# Iris_v1.net
KiCad netlist of a schematic drawn in EAGLE
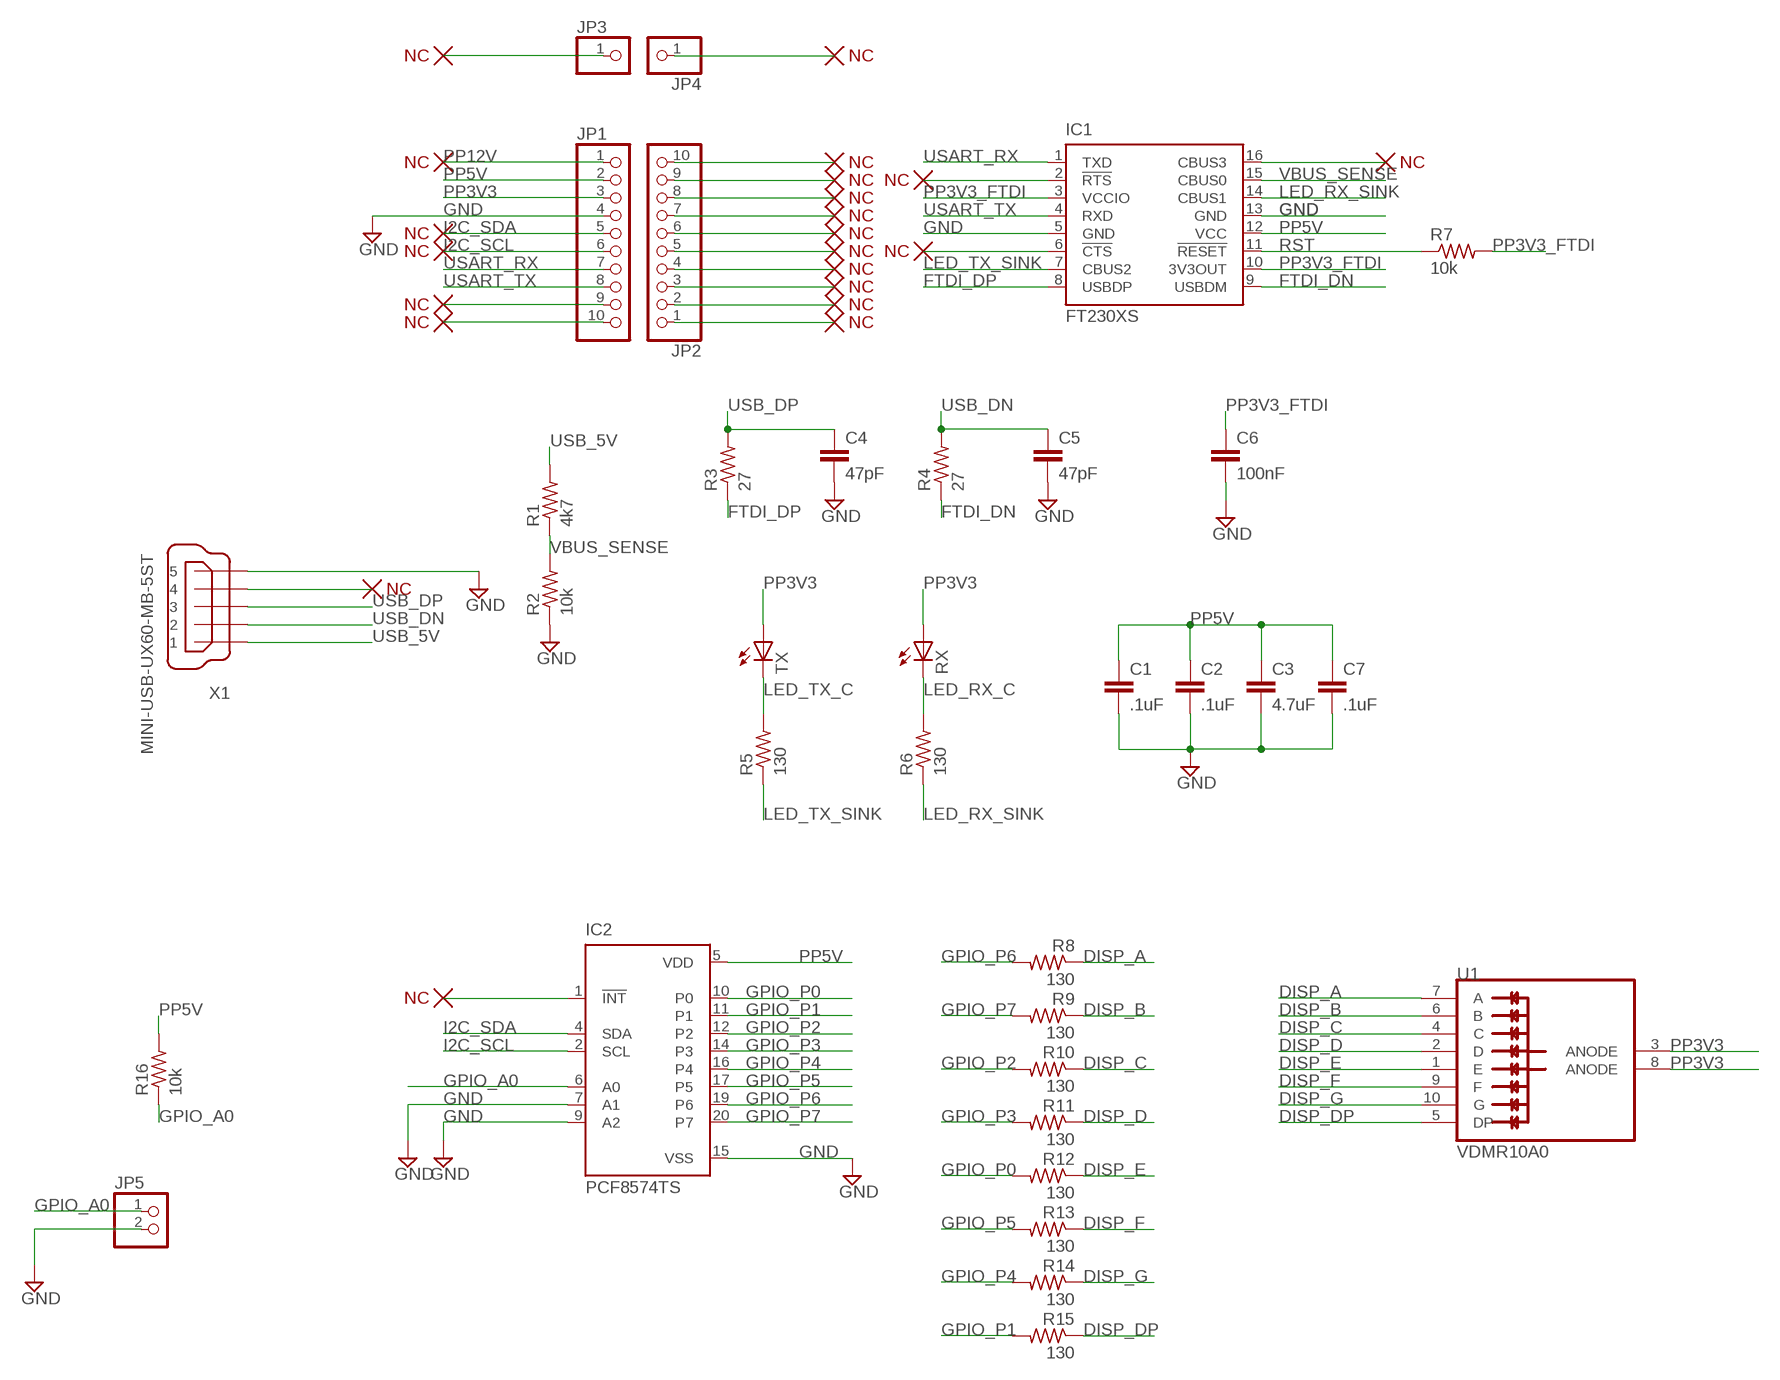
[diagram p0: schematic, sheet 1]

(export (version "E")
  (design (tool "Eeschema 10.0.6"))
  (components
    (comp (ref "C1")
      (value ".1uF")
      (footprint "eagle-import:C0402")
      (libsource (lib "eagle-import") (part "C-EUC0402"))
    )
    (comp (ref "C2")
      (value ".1uF")
      (footprint "eagle-import:C0402")
      (libsource (lib "eagle-import") (part "C-EUC0402"))
    )
    (comp (ref "C3")
      (value "4.7uF")
      (footprint "eagle-import:C0603")
      (libsource (lib "eagle-import") (part "C-EUC0603"))
    )
    (comp (ref "C4")
      (value "47pF")
      (footprint "eagle-import:C0402")
      (libsource (lib "eagle-import") (part "C-EUC0402"))
    )
    (comp (ref "C5")
      (value "47pF")
      (footprint "eagle-import:C0402")
      (libsource (lib "eagle-import") (part "C-EUC0402"))
    )
    (comp (ref "C6")
      (value "100nF")
      (footprint "eagle-import:C0402")
      (libsource (lib "eagle-import") (part "C-EUC0402"))
    )
    (comp (ref "C7")
      (value ".1uF")
      (footprint "eagle-import:C0402")
      (libsource (lib "eagle-import") (part "C-EUC0402"))
    )
    (comp (ref "IC1")
      (value "FT230XS")
      (footprint "eagle-import:SSOP16")
      (libsource (lib "eagle-import") (part "FT230XS"))
    )
    (comp (ref "IC2")
      (value "PCF8574TS")
      (footprint "eagle-import:SSOP20")
      (fields (field (name "MPN") "PCF8574TS/3,118"))
      (libsource (lib "eagle-import") (part "PCF8574TS"))
    )
    (comp (ref "JP1")
      (value "PINHD-1X10")
      (footprint "eagle-import:1X10")
      (libsource (lib "eagle-import") (part "PINHD-1X10"))
    )
    (comp (ref "JP2")
      (value "PINHD-1X10")
      (footprint "eagle-import:1X10")
      (libsource (lib "eagle-import") (part "PINHD-1X10"))
    )
    (comp (ref "JP3")
      (value "PINHD-1X1")
      (footprint "eagle-import:1X01")
      (libsource (lib "eagle-import") (part "PINHD-1X1"))
    )
    (comp (ref "JP4")
      (value "PINHD-1X1")
      (footprint "eagle-import:1X01")
      (libsource (lib "eagle-import") (part "PINHD-1X1"))
    )
    (comp (ref "JP5")
      (value "PINHD-1X2")
      (footprint "eagle-import:1X02")
      (libsource (lib "eagle-import") (part "PINHD-1X2"))
    )
    (comp (ref "R1")
      (value "4k7")
      (footprint "eagle-import:R0402")
      (libsource (lib "eagle-import") (part "resistor_R-US_R0402"))
    )
    (comp (ref "R2")
      (value "10k")
      (footprint "eagle-import:R0402")
      (libsource (lib "eagle-import") (part "resistor_R-US_R0402"))
    )
    (comp (ref "R3")
      (value "27")
      (footprint "eagle-import:R0402")
      (libsource (lib "eagle-import") (part "resistor_R-US_R0402"))
    )
    (comp (ref "R4")
      (value "27")
      (footprint "eagle-import:R0402")
      (libsource (lib "eagle-import") (part "resistor_R-US_R0402"))
    )
    (comp (ref "R5")
      (value "130")
      (footprint "eagle-import:R0402")
      (libsource (lib "eagle-import") (part "resistor_R-US_R0402"))
    )
    (comp (ref "R6")
      (value "130")
      (footprint "eagle-import:R0402")
      (libsource (lib "eagle-import") (part "resistor_R-US_R0402"))
    )
    (comp (ref "R7")
      (value "10k")
      (footprint "eagle-import:R0603")
      (libsource (lib "eagle-import") (part "R-US_R0603"))
    )
    (comp (ref "R8")
      (value "130")
      (footprint "eagle-import:R0402")
      (libsource (lib "eagle-import") (part "resistor_R-US_R0402"))
    )
    (comp (ref "R9")
      (value "130")
      (footprint "eagle-import:R0402")
      (libsource (lib "eagle-import") (part "resistor_R-US_R0402"))
    )
    (comp (ref "R10")
      (value "130")
      (footprint "eagle-import:R0402")
      (libsource (lib "eagle-import") (part "resistor_R-US_R0402"))
    )
    (comp (ref "R11")
      (value "130")
      (footprint "eagle-import:R0402")
      (libsource (lib "eagle-import") (part "resistor_R-US_R0402"))
    )
    (comp (ref "R12")
      (value "130")
      (footprint "eagle-import:R0402")
      (libsource (lib "eagle-import") (part "resistor_R-US_R0402"))
    )
    (comp (ref "R13")
      (value "130")
      (footprint "eagle-import:R0402")
      (libsource (lib "eagle-import") (part "resistor_R-US_R0402"))
    )
    (comp (ref "R14")
      (value "130")
      (footprint "eagle-import:R0402")
      (libsource (lib "eagle-import") (part "resistor_R-US_R0402"))
    )
    (comp (ref "R15")
      (value "130")
      (footprint "eagle-import:R0402")
      (libsource (lib "eagle-import") (part "resistor_R-US_R0402"))
    )
    (comp (ref "R16")
      (value "10k")
      (footprint "eagle-import:R0402")
      (libsource (lib "eagle-import") (part "resistor_R-US_R0402"))
    )
    (comp (ref "RX")
      (value "LEDCHIP-LED0603")
      (footprint "eagle-import:CHIP-LED0603")
      (libsource (lib "eagle-import") (part "LEDCHIP-LED0603"))
    )
    (comp (ref "TX")
      (value "LEDCHIP-LED0603")
      (footprint "eagle-import:CHIP-LED0603")
      (libsource (lib "eagle-import") (part "LEDCHIP-LED0603"))
    )
    (comp (ref "U1")
      (value "VDMR10.0")
      (footprint "eagle-import:VDMR10A0")
      (libsource (lib "eagle-import") (part "VDMR10.0"))
    )
    (comp (ref "X1")
      (value "MINI-USB-UX60-MB-5ST")
      (footprint "eagle-import:UX60-MB-5ST")
      (libsource (lib "eagle-import") (part "MINI-USB-UX60-MB-5ST"))
    )
  )
  (nets
    (net (code "1") (name "/DISP_A") (class "Default")
      (node (ref "R8") (pin "1") (pinfunction "1_1") (pintype "passive"))
      (node (ref "U1") (pin "7") (pinfunction "A_7") (pintype "bidirectional"))
    )
    (net (code "2") (name "/DISP_B") (class "Default")
      (node (ref "R9") (pin "1") (pinfunction "1_1") (pintype "passive"))
      (node (ref "U1") (pin "6") (pinfunction "B_6") (pintype "bidirectional"))
    )
    (net (code "3") (name "/DISP_C") (class "Default")
      (node (ref "R10") (pin "1") (pinfunction "1_1") (pintype "passive"))
      (node (ref "U1") (pin "4") (pinfunction "C_4") (pintype "bidirectional"))
    )
    (net (code "4") (name "/DISP_D") (class "Default")
      (node (ref "R11") (pin "1") (pinfunction "1_1") (pintype "passive"))
      (node (ref "U1") (pin "2") (pinfunction "D_2") (pintype "bidirectional"))
    )
    (net (code "5") (name "/DISP_DP") (class "Default")
      (node (ref "R15") (pin "1") (pinfunction "1_1") (pintype "passive"))
      (node (ref "U1") (pin "5") (pinfunction "DP_5") (pintype "bidirectional"))
    )
    (net (code "6") (name "/DISP_E") (class "Default")
      (node (ref "R12") (pin "1") (pinfunction "1_1") (pintype "passive"))
      (node (ref "U1") (pin "1") (pinfunction "E_1") (pintype "bidirectional"))
    )
    (net (code "7") (name "/DISP_F") (class "Default")
      (node (ref "R13") (pin "1") (pinfunction "1_1") (pintype "passive"))
      (node (ref "U1") (pin "9") (pinfunction "F_9") (pintype "bidirectional"))
    )
    (net (code "8") (name "/DISP_G") (class "Default")
      (node (ref "R14") (pin "1") (pinfunction "1_1") (pintype "passive"))
      (node (ref "U1") (pin "10") (pinfunction "G_10") (pintype "bidirectional"))
    )
    (net (code "9") (name "/FTDI_DN") (class "Default")
      (node (ref "IC1") (pin "9") (pinfunction "USBDM_9") (pintype "input"))
      (node (ref "R4") (pin "1") (pinfunction "1_1") (pintype "passive"))
    )
    (net (code "10") (name "/FTDI_DP") (class "Default")
      (node (ref "IC1") (pin "8") (pinfunction "USBDP_8") (pintype "input"))
      (node (ref "R3") (pin "1") (pinfunction "1_1") (pintype "passive"))
    )
    (net (code "11") (name "/GPIO_A0") (class "Default")
      (node (ref "IC2") (pin "6") (pinfunction "A0_6") (pintype "input"))
      (node (ref "JP5") (pin "1") (pinfunction "1_1") (pintype "passive"))
      (node (ref "R16") (pin "1") (pinfunction "1_1") (pintype "passive"))
    )
    (net (code "12") (name "/GPIO_P0") (class "Default")
      (node (ref "IC2") (pin "10") (pinfunction "P0_10") (pintype "bidirectional"))
      (node (ref "R12") (pin "2") (pinfunction "2_2") (pintype "passive"))
    )
    (net (code "13") (name "/GPIO_P1") (class "Default")
      (node (ref "IC2") (pin "11") (pinfunction "P1_11") (pintype "bidirectional"))
      (node (ref "R15") (pin "2") (pinfunction "2_2") (pintype "passive"))
    )
    (net (code "14") (name "/GPIO_P2") (class "Default")
      (node (ref "IC2") (pin "12") (pinfunction "P2_12") (pintype "bidirectional"))
      (node (ref "R10") (pin "2") (pinfunction "2_2") (pintype "passive"))
    )
    (net (code "15") (name "/GPIO_P3") (class "Default")
      (node (ref "IC2") (pin "14") (pinfunction "P3_14") (pintype "bidirectional"))
      (node (ref "R11") (pin "2") (pinfunction "2_2") (pintype "passive"))
    )
    (net (code "16") (name "/GPIO_P4") (class "Default")
      (node (ref "IC2") (pin "16") (pinfunction "P4_16") (pintype "bidirectional"))
      (node (ref "R14") (pin "2") (pinfunction "2_2") (pintype "passive"))
    )
    (net (code "17") (name "/GPIO_P5") (class "Default")
      (node (ref "IC2") (pin "17") (pinfunction "P5_17") (pintype "bidirectional"))
      (node (ref "R13") (pin "2") (pinfunction "2_2") (pintype "passive"))
    )
    (net (code "18") (name "/GPIO_P6") (class "Default")
      (node (ref "IC2") (pin "19") (pinfunction "P6_19") (pintype "bidirectional"))
      (node (ref "R8") (pin "2") (pinfunction "2_2") (pintype "passive"))
    )
    (net (code "19") (name "/GPIO_P7") (class "Default")
      (node (ref "IC2") (pin "20") (pinfunction "P7_20") (pintype "bidirectional"))
      (node (ref "R9") (pin "2") (pinfunction "2_2") (pintype "passive"))
    )
    (net (code "20") (name "/I2C_SCL") (class "Default")
      (node (ref "IC2") (pin "2") (pinfunction "SCL_2") (pintype "input"))
      (node (ref "JP1") (pin "6") (pinfunction "6_6") (pintype "passive"))
    )
    (net (code "21") (name "/I2C_SDA") (class "Default")
      (node (ref "IC2") (pin "4") (pinfunction "SDA_4") (pintype "bidirectional"))
      (node (ref "JP1") (pin "5") (pinfunction "5_5") (pintype "passive"))
    )
    (net (code "22") (name "/LED_RX_C") (class "Default")
      (node (ref "R6") (pin "2") (pinfunction "2_2") (pintype "passive"))
      (node (ref "RX") (pin "C") (pinfunction "C_C") (pintype "passive"))
    )
    (net (code "23") (name "/LED_RX_SINK") (class "Default")
      (node (ref "IC1") (pin "14") (pinfunction "CBUS1_14") (pintype "bidirectional"))
      (node (ref "R6") (pin "1") (pinfunction "1_1") (pintype "passive"))
    )
    (net (code "24") (name "/LED_TX_C") (class "Default")
      (node (ref "R5") (pin "2") (pinfunction "2_2") (pintype "passive"))
      (node (ref "TX") (pin "C") (pinfunction "C_C") (pintype "passive"))
    )
    (net (code "25") (name "/LED_TX_SINK") (class "Default")
      (node (ref "IC1") (pin "7") (pinfunction "CBUS2_7") (pintype "bidirectional"))
      (node (ref "R5") (pin "1") (pinfunction "1_1") (pintype "passive"))
    )
    (net (code "26") (name "/PP3V3") (class "Default")
      (node (ref "JP1") (pin "3") (pinfunction "3_3") (pintype "passive"))
      (node (ref "RX") (pin "A") (pinfunction "A_A") (pintype "passive"))
      (node (ref "TX") (pin "A") (pinfunction "A_A") (pintype "passive"))
      (node (ref "U1") (pin "3") (pinfunction "ANODE_3") (pintype "bidirectional"))
      (node (ref "U1") (pin "8") (pinfunction "ANODE_8") (pintype "bidirectional"))
    )
    (net (code "27") (name "/PP3V3_FTDI") (class "Default")
      (node (ref "C6") (pin "1") (pinfunction "1_1") (pintype "passive"))
      (node (ref "IC1") (pin "10") (pinfunction "3V3OUT_10") (pintype "output"))
      (node (ref "IC1") (pin "3") (pinfunction "VCCIO_3") (pintype "power_in"))
      (node (ref "R7") (pin "2") (pinfunction "2_2") (pintype "passive"))
    )
    (net (code "28") (name "/PP5V") (class "Default")
      (node (ref "C1") (pin "1") (pinfunction "1_1") (pintype "passive"))
      (node (ref "C2") (pin "1") (pinfunction "1_1") (pintype "passive"))
      (node (ref "C3") (pin "1") (pinfunction "1_1") (pintype "passive"))
      (node (ref "C7") (pin "1") (pinfunction "1_1") (pintype "passive"))
      (node (ref "IC1") (pin "12") (pinfunction "VCC_12") (pintype "power_in"))
      (node (ref "IC2") (pin "5") (pinfunction "VDD_5") (pintype "power_in"))
      (node (ref "JP1") (pin "2") (pinfunction "2_2") (pintype "passive"))
      (node (ref "R16") (pin "2") (pinfunction "2_2") (pintype "passive"))
    )
    (net (code "29") (name "/PP12V") (class "Default")
      (node (ref "JP1") (pin "1") (pinfunction "1_1") (pintype "passive"))
    )
    (net (code "30") (name "/RST") (class "Default")
      (node (ref "IC1") (pin "11") (pinfunction "~{RESET}_11") (pintype "input"))
      (node (ref "R7") (pin "1") (pinfunction "1_1") (pintype "passive"))
    )
    (net (code "31") (name "/USART_RX") (class "Default")
      (node (ref "IC1") (pin "1") (pinfunction "TXD_1") (pintype "output"))
      (node (ref "JP1") (pin "7") (pinfunction "7_7") (pintype "passive"))
    )
    (net (code "32") (name "/USART_TX") (class "Default")
      (node (ref "IC1") (pin "4") (pinfunction "RXD_4") (pintype "input"))
      (node (ref "JP1") (pin "8") (pinfunction "8_8") (pintype "passive"))
    )
    (net (code "33") (name "/USB_5V") (class "Default")
      (node (ref "R1") (pin "2") (pinfunction "2_2") (pintype "passive"))
      (node (ref "X1") (pin "1") (pinfunction "1_1") (pintype "input"))
    )
    (net (code "34") (name "/USB_DN") (class "Default")
      (node (ref "C5") (pin "1") (pinfunction "1_1") (pintype "passive"))
      (node (ref "R4") (pin "2") (pinfunction "2_2") (pintype "passive"))
      (node (ref "X1") (pin "2") (pinfunction "2_2") (pintype "input"))
    )
    (net (code "35") (name "/USB_DP") (class "Default")
      (node (ref "C4") (pin "1") (pinfunction "1_1") (pintype "passive"))
      (node (ref "R3") (pin "2") (pinfunction "2_2") (pintype "passive"))
      (node (ref "X1") (pin "3") (pinfunction "3_3") (pintype "input"))
    )
    (net (code "36") (name "/VBUS_SENSE") (class "Default")
      (node (ref "IC1") (pin "15") (pinfunction "CBUS0_15") (pintype "bidirectional"))
      (node (ref "R1") (pin "1") (pinfunction "1_1") (pintype "passive"))
      (node (ref "R2") (pin "2") (pinfunction "2_2") (pintype "passive"))
    )
    (net (code "37") (name "GND") (class "Default")
      (node (ref "C1") (pin "2") (pinfunction "2_2") (pintype "passive"))
      (node (ref "C2") (pin "2") (pinfunction "2_2") (pintype "passive"))
      (node (ref "C3") (pin "2") (pinfunction "2_2") (pintype "passive"))
      (node (ref "C4") (pin "2") (pinfunction "2_2") (pintype "passive"))
      (node (ref "C5") (pin "2") (pinfunction "2_2") (pintype "passive"))
      (node (ref "C6") (pin "2") (pinfunction "2_2") (pintype "passive"))
      (node (ref "C7") (pin "2") (pinfunction "2_2") (pintype "passive"))
      (node (ref "IC1") (pin "13") (pinfunction "GND_13") (pintype "power_in"))
      (node (ref "IC1") (pin "5") (pinfunction "GND_5") (pintype "power_in"))
      (node (ref "IC2") (pin "15") (pinfunction "VSS_15") (pintype "power_in"))
      (node (ref "IC2") (pin "7") (pinfunction "A1_7") (pintype "input"))
      (node (ref "IC2") (pin "9") (pinfunction "A2_9") (pintype "input"))
      (node (ref "JP1") (pin "4") (pinfunction "4_4") (pintype "passive"))
      (node (ref "JP5") (pin "2") (pinfunction "2_2") (pintype "passive"))
      (node (ref "R2") (pin "1") (pinfunction "1_1") (pintype "passive"))
      (node (ref "X1") (pin "5") (pinfunction "5_5") (pintype "input"))
    )
    (net (code "38") (name "unconnected-(IC1-CBUS3-Pad16)") (class "Default")
      (node (ref "IC1") (pin "16") (pinfunction "CBUS3_16") (pintype "bidirectional"))
    )
    (net (code "39") (name "unconnected-(IC1-~{CTS}-Pad6)") (class "Default")
      (node (ref "IC1") (pin "6") (pinfunction "~{CTS}_6") (pintype "input"))
    )
    (net (code "40") (name "unconnected-(IC1-~{RTS}-Pad2)") (class "Default")
      (node (ref "IC1") (pin "2") (pinfunction "~{RTS}_2") (pintype "output"))
    )
    (net (code "41") (name "unconnected-(IC2-~{INT}-Pad1)") (class "Default")
      (node (ref "IC2") (pin "1") (pinfunction "~{INT}_1") (pintype "output"))
    )
    (net (code "42") (name "unconnected-(JP1-Pad9)") (class "Default")
      (node (ref "JP1") (pin "9") (pinfunction "9_9") (pintype "passive"))
    )
    (net (code "43") (name "unconnected-(JP1-Pad10)") (class "Default")
      (node (ref "JP1") (pin "10") (pinfunction "10_10") (pintype "passive"))
    )
    (net (code "44") (name "unconnected-(JP2-Pad1)") (class "Default")
      (node (ref "JP2") (pin "1") (pinfunction "1_1") (pintype "passive"))
    )
    (net (code "45") (name "unconnected-(JP2-Pad2)") (class "Default")
      (node (ref "JP2") (pin "2") (pinfunction "2_2") (pintype "passive"))
    )
    (net (code "46") (name "unconnected-(JP2-Pad3)") (class "Default")
      (node (ref "JP2") (pin "3") (pinfunction "3_3") (pintype "passive"))
    )
    (net (code "47") (name "unconnected-(JP2-Pad4)") (class "Default")
      (node (ref "JP2") (pin "4") (pinfunction "4_4") (pintype "passive"))
    )
    (net (code "48") (name "unconnected-(JP2-Pad5)") (class "Default")
      (node (ref "JP2") (pin "5") (pinfunction "5_5") (pintype "passive"))
    )
    (net (code "49") (name "unconnected-(JP2-Pad6)") (class "Default")
      (node (ref "JP2") (pin "6") (pinfunction "6_6") (pintype "passive"))
    )
    (net (code "50") (name "unconnected-(JP2-Pad7)") (class "Default")
      (node (ref "JP2") (pin "7") (pinfunction "7_7") (pintype "passive"))
    )
    (net (code "51") (name "unconnected-(JP2-Pad8)") (class "Default")
      (node (ref "JP2") (pin "8") (pinfunction "8_8") (pintype "passive"))
    )
    (net (code "52") (name "unconnected-(JP2-Pad9)") (class "Default")
      (node (ref "JP2") (pin "9") (pinfunction "9_9") (pintype "passive"))
    )
    (net (code "53") (name "unconnected-(JP2-Pad10)") (class "Default")
      (node (ref "JP2") (pin "10") (pinfunction "10_10") (pintype "passive"))
    )
    (net (code "54") (name "unconnected-(JP3-Pad1)") (class "Default")
      (node (ref "JP3") (pin "1") (pinfunction "1_1") (pintype "passive"))
    )
    (net (code "55") (name "unconnected-(JP4-Pad1)") (class "Default")
      (node (ref "JP4") (pin "1") (pinfunction "1_1") (pintype "passive"))
    )
    (net (code "56") (name "unconnected-(X1-Pad4)") (class "Default")
      (node (ref "X1") (pin "4") (pinfunction "4_4") (pintype "input"))
    )
  )
)
